# H07R1x_Backend.net
KiCad netlist of a schematic drawn in Altium Designer
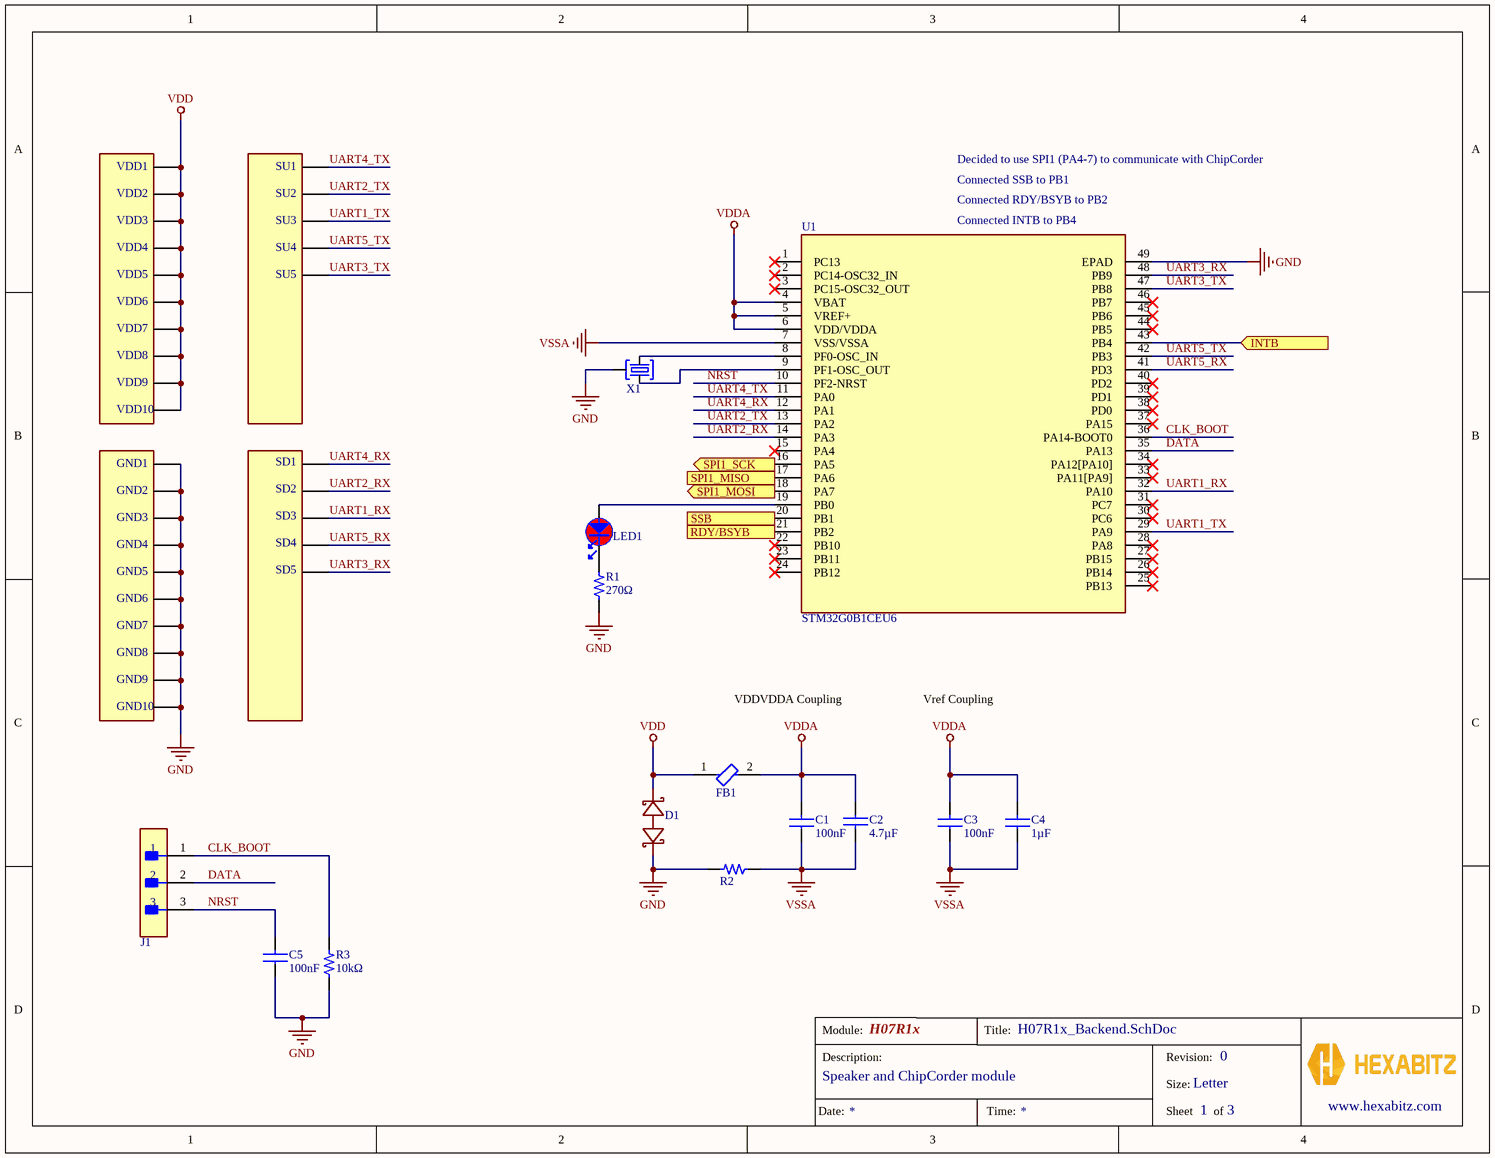
[diagram p0: H07R1x_Backend.SchDoc]

(export (version "E")
  (design (tool "Eeschema 10.0.6"))
  (components
    (comp (ref "C1")
      (value "100nF")
      (footprint "C0603")
      (fields
        (field (name "MANUFACTURER") "Samsung Electro-Mechanics")
        (field (name "MANUFACTURER PART NUMBER") "CL10B104KA8NNNC")
        (field (name "TOLERANCE") "10%")
      )
      (libsource (lib "Hexabitz Altium Library") (part "generic Capacitor"))
    )
    (comp (ref "C2")
      (value "4.7µF")
      (footprint "C0805")
      (fields
        (field (name "MANUFACTURER") "Samsung Electro-Mechanics")
        (field (name "MANUFACTURER PART NUMBER") "CL21X475KAQNNNE")
        (field (name "TOLERANCE") "10%")
      )
      (libsource (lib "Hexabitz Altium Library") (part "generic Capacitor"))
    )
    (comp (ref "C3")
      (value "100nF")
      (footprint "C0603")
      (fields
        (field (name "MANUFACTURER") "Samsung Electro-Mechanics")
        (field (name "MANUFACTURER PART NUMBER") "CL10B104KA8NNNC")
        (field (name "TOLERANCE") "10%")
      )
      (libsource (lib "Hexabitz Altium Library") (part "generic Capacitor"))
    )
    (comp (ref "C4")
      (value "1µF")
      (footprint "C0805")
      (description "Ceramic Capacitor, Ceramic, 16V, 10% +Tol, 10% -Tol, X7R, 15% TC, 1uF, Surface Mount, 0805")
      (fields
        (field (name "MANUFACTURER") "Yageo Group")
        (field (name "MANUFACTURER PART NUMBER") "CC0805KKX7R7BB105")
      )
      (libsource (lib "Hexabitz Altium Library") (part "generic Capacitor"))
    )
    (comp (ref "C5")
      (value "100nF")
      (footprint "C0603")
      (fields
        (field (name "MANUFACTURER") "Samsung Electro-Mechanics")
        (field (name "MANUFACTURER PART NUMBER") "CL10B104KA8NNNC")
        (field (name "TOLERANCE") "10%")
      )
      (libsource (lib "Hexabitz Altium Library") (part "generic Capacitor"))
    )
    (comp (ref "D1")
      (value "CDSOD323-T03SC")
      (footprint "SOD2513X114N")
      (description "A 3V, 350W, bi-directional, standard capacitance, SOD323 pkg TVS Diode ¦ Bourns CDSOD323-T03SC")
      (fields (field (name "MANUFACTURER") "Bourns"))
      (libsource (lib "Hexabitz Altium Library") (part "CDSOD323-T03SC"))
    )
    (comp (ref "FB1")
      (value "MMZ1608Y300B")
      (footprint "FP-MMZ1608-0_8-MFG")
      (description "Ferrite Beads 0603 30ohms 1500mA Signal Line AEC-Q200")
      (fields
        (field (name "MANUFACTURER") "TDK")
        (field (name "MANUFACTURER PART NUMBER") "MMZ1608Y300BTD25")
      )
      (libsource (lib "Hexabitz Altium Library") (part "MMZ1608Y300B"))
    )
    (comp (ref "GND1")
      (value "HEXABIT_UART_PORT")
      (footprint "HEXABIT_POWER_PORT_D")
      (libsource (lib "hexabitz_connectors.Library") (part "HEXABIT_POWER_PORT_D"))
    )
    (comp (ref "GND2")
      (value "HEXABIT_UART_PORT")
      (footprint "HEXABIT_POWER_PORT_D")
      (libsource (lib "hexabitz_connectors.Library") (part "HEXABIT_POWER_PORT_D"))
    )
    (comp (ref "GND3")
      (value "HEXABIT_UART_PORT")
      (footprint "HEXABIT_POWER_PORT_D_300R")
      (libsource (lib "hexabitz_connectors.Library") (part "HEXABIT_POWER_PORT_D_300R"))
    )
    (comp (ref "GND4")
      (value "HEXABIT_UART_PORT")
      (footprint "HEXABIT_POWER_PORT_D")
      (libsource (lib "hexabitz_connectors.Library") (part "HEXABIT_POWER_PORT_D"))
    )
    (comp (ref "GND5")
      (value "HEXABIT_UART_PORT")
      (footprint "HEXABIT_POWER_PORT_D")
      (libsource (lib "hexabitz_connectors.Library") (part "HEXABIT_POWER_PORT_D"))
    )
    (comp (ref "GND6")
      (value "HEXABIT_UART_PORT")
      (footprint "HEXABIT_POWER_PORT_D")
      (libsource (lib "hexabitz_connectors.Library") (part "HEXABIT_POWER_PORT_D"))
    )
    (comp (ref "GND7")
      (value "HEXABIT_UART_PORT")
      (footprint "HEXABIT_POWER_PORT_D")
      (libsource (lib "hexabitz_connectors.Library") (part "HEXABIT_POWER_PORT_D"))
    )
    (comp (ref "GND8")
      (value "HEXABIT_UART_PORT")
      (footprint "HEXABIT_POWER_PORT_D_300L")
      (libsource (lib "hexabitz_connectors.Library") (part "HEXABIT_POWER_PORT_D_300L"))
    )
    (comp (ref "GND9")
      (value "HEXABIT_UART_PORT")
      (footprint "HEXABIT_POWER_PORT_D")
      (libsource (lib "hexabitz_connectors.Library") (part "HEXABIT_POWER_PORT_D"))
    )
    (comp (ref "GND10")
      (value "HEXABIT_UART_PORT")
      (footprint "HEXABIT_POWER_PORT_D")
      (libsource (lib "hexabitz_connectors.Library") (part "HEXABIT_POWER_PORT_D"))
    )
    (comp (ref "J1")
      (value "TSW-103-14-G-S")
      (footprint "FP-TSW-103-14-G-S-MFG")
      (description "CONN HEADER VERT 3POS 2.54MM")
      (libsource (lib "Altium Content Vault") (part "cd3439d6ef35ae5d9b27ec4fdd3e828"))
    )
    (comp (ref "LED1")
      (value "VLMS1300-GS08")
      (footprint "FP-6_541-5092_01-4-MFG")
      (description "LED Uni-Color Super Red 639nm 2-Pin Chip 0603(1608Metric) T/R")
      (fields (field (name "MANUFACTURER") "Vishay Semiconductors"))
      (libsource (lib "Hexabitz Altium Library") (part "VLMS1300-GS08"))
    )
    (comp (ref "R1")
      (value "270Ω")
      (footprint "R0603")
      (description "Res Thick Film 0603 270 Ohm 5% 0.1W(1/10W) ±200ppm/C Pad SMD Automotive T/R")
      (fields
        (field (name "MANUFACTURER") "Panasonic")
        (field (name "MANUFACTURER PART NUMBER") "ERJ-3GEYJ271V")
      )
      (libsource (lib "") (part "generic Resistor_1"))
    )
    (comp (ref "R2")
      (value "Manufacturer Part Number")
      (footprint "R0603")
      (libsource (lib "Hexabitz Altium Library") (part "generic Resistor"))
    )
    (comp (ref "R3")
      (value "10kΩ")
      (footprint "R0603")
      (description "100mW Thick Film Resistors ±100ppm/℃ ±1% 10kΩ 0603 Chip Resistor - Surface Mount ROHS")
      (fields
        (field (name "MANUFACTURER") "Yageo Group")
        (field (name "MANUFACTURER PART NUMBER") "RC0603FR-0710KL")
      )
      (libsource (lib "") (part "generic Resistor_2"))
    )
    (comp (ref "SD1")
      (value "HEXABIT_UART_PORT")
      (footprint "HEXABIT_UART_PORT_D")
      (libsource (lib "hexabitz_connectors.Library") (part "HEXABIT_UART_PORT_D"))
    )
    (comp (ref "SD2")
      (value "HEXABIT_UART_PORT")
      (footprint "HEXABIT_UART_PORT_D")
      (libsource (lib "hexabitz_connectors.Library") (part "HEXABIT_UART_PORT_D"))
    )
    (comp (ref "SD3")
      (value "HEXABIT_UART_PORT")
      (footprint "HEXABIT_UART_PORT_D")
      (libsource (lib "hexabitz_connectors.Library") (part "HEXABIT_UART_PORT_D"))
    )
    (comp (ref "SD4")
      (value "HEXABIT_UART_PORT")
      (footprint "HEXABIT_UART_PORT_D")
      (libsource (lib "hexabitz_connectors.Library") (part "HEXABIT_UART_PORT_D"))
    )
    (comp (ref "SD5")
      (value "HEXABIT_UART_PORT")
      (footprint "HEXABIT_UART_PORT_D")
      (libsource (lib "hexabitz_connectors.Library") (part "HEXABIT_UART_PORT_D"))
    )
    (comp (ref "SU1")
      (value "HEXABIT_UART_PORT")
      (footprint "HEXABIT_UART_PORT_U")
      (libsource (lib "hexabitz_connectors.Library") (part "HEXABIT_UART_PORT_U"))
    )
    (comp (ref "SU2")
      (value "HEXABIT_UART_PORT")
      (footprint "HEXABIT_UART_PORT_U")
      (libsource (lib "hexabitz_connectors.Library") (part "HEXABIT_UART_PORT_U"))
    )
    (comp (ref "SU3")
      (value "HEXABIT_UART_PORT")
      (footprint "HEXABIT_UART_PORT_U")
      (libsource (lib "hexabitz_connectors.Library") (part "HEXABIT_UART_PORT_U"))
    )
    (comp (ref "SU4")
      (value "HEXABIT_UART_PORT")
      (footprint "HEXABIT_UART_PORT_U")
      (libsource (lib "hexabitz_connectors.Library") (part "HEXABIT_UART_PORT_U"))
    )
    (comp (ref "SU5")
      (value "HEXABIT_UART_PORT")
      (footprint "HEXABIT_UART_PORT_U")
      (libsource (lib "hexabitz_connectors.Library") (part "HEXABIT_UART_PORT_U"))
    )
    (comp (ref "U1")
      (value "STM32G0B1CEU6")
      (footprint "QFN50P700X700X65-49N-D")
      (description "MCU 32-bit ARM Cortex M0+ RISC 512KB Flash 1.8V/2.5V/3.3V 48-Pin UFQFPN EP Tray")
      (fields
        (field (name "MANUFACTURER") "STMicroelectronics")
        (field (name "MANUFACTURER PART NUMBER") "STM32G0B1CEU6")
      )
      (libsource (lib "Hexabitz Altium Library") (part "STM32G0B1CEU6"))
    )
    (comp (ref "VDD1")
      (value "HEXABIT_UART_PORT")
      (footprint "HEXABIT_POWER_PORT_U")
      (libsource (lib "hexabitz_connectors.Library") (part "HEXABIT_POWER_PORT_U"))
    )
    (comp (ref "VDD2")
      (value "HEXABIT_UART_PORT")
      (footprint "HEXABIT_POWER_PORT_U")
      (libsource (lib "hexabitz_connectors.Library") (part "HEXABIT_POWER_PORT_U"))
    )
    (comp (ref "VDD3")
      (value "HEXABIT_UART_PORT")
      (footprint "HEXABIT_POWER_PORT_U_300R")
      (libsource (lib "hexabitz_connectors.Library") (part "HEXABIT_POWER_PORT_U_300R"))
    )
    (comp (ref "VDD4")
      (value "HEXABIT_UART_PORT")
      (footprint "HEXABIT_POWER_PORT_U")
      (libsource (lib "hexabitz_connectors.Library") (part "HEXABIT_POWER_PORT_U"))
    )
    (comp (ref "VDD5")
      (value "HEXABIT_UART_PORT")
      (footprint "HEXABIT_POWER_PORT_U")
      (libsource (lib "hexabitz_connectors.Library") (part "HEXABIT_POWER_PORT_U"))
    )
    (comp (ref "VDD6")
      (value "HEXABIT_UART_PORT")
      (footprint "HEXABIT_POWER_PORT_U")
      (libsource (lib "hexabitz_connectors.Library") (part "HEXABIT_POWER_PORT_U"))
    )
    (comp (ref "VDD7")
      (value "HEXABIT_UART_PORT")
      (footprint "HEXABIT_POWER_PORT_U")
      (libsource (lib "hexabitz_connectors.Library") (part "HEXABIT_POWER_PORT_U"))
    )
    (comp (ref "VDD8")
      (value "HEXABIT_UART_PORT")
      (footprint "HEXABIT_POWER_PORT_U_300L")
      (libsource (lib "hexabitz_connectors.Library") (part "HEXABIT_POWER_PORT_U_300L"))
    )
    (comp (ref "VDD9")
      (value "HEXABIT_UART_PORT")
      (footprint "HEXABIT_POWER_PORT_U")
      (libsource (lib "hexabitz_connectors.Library") (part "HEXABIT_POWER_PORT_U"))
    )
    (comp (ref "VDD10")
      (value "HEXABIT_UART_PORT")
      (footprint "HEXABIT_POWER_PORT_U")
      (libsource (lib "hexabitz_connectors.Library") (part "HEXABIT_POWER_PORT_U"))
    )
    (comp (ref "X1")
      (value "CSTCE8M00G52Z-R0")
      (footprint "XTALL_CSTCE8M00G52")
      (description "Ceramic Resonator 8MHz ±0.5% (Tol) ±0.2% (Stability) 10pF 40Ohm 3-Pin CSMD T/R")
      (fields (field (name "MANUFACTURER") "Murata") (field (name "TOLERANCE") "0.5%"))
      (libsource (lib "Hexabitz Altium Library") (part "CSTCE8M00G52Z-R0"))
    )
  )
  (nets
    (net (code "1") (name "/CLK_BOOT") (class "Default")
      (node (ref "J1") (pin "1") (pinfunction "1_1") (pintype "passive"))
      (node (ref "R3") (pin "1") (pinfunction "1_1") (pintype "passive"))
      (node (ref "U1") (pin "36") (pinfunction "PA14-BOOT0_36") (pintype "passive"))
    )
    (net (code "2") (name "/DATA") (class "Default")
      (node (ref "J1") (pin "2") (pinfunction "2_2") (pintype "passive"))
      (node (ref "U1") (pin "35") (pinfunction "PA13_35") (pintype "passive"))
    )
    (net (code "3") (name "/INTB") (class "Default")
      (node (ref "U1") (pin "43") (pinfunction "PB4_43") (pintype "passive"))
    )
    (net (code "4") (name "/NRST") (class "Default")
      (node (ref "C5") (pin "2") (pinfunction "2_2") (pintype "passive"))
      (node (ref "J1") (pin "3") (pinfunction "3_3") (pintype "passive"))
      (node (ref "U1") (pin "10") (pinfunction "PF2-NRST_10") (pintype "passive"))
    )
    (net (code "5") (name "/RDY{slash}BSYB") (class "Default")
      (node (ref "U1") (pin "21") (pinfunction "PB2_21") (pintype "passive"))
    )
    (net (code "6") (name "/SPI1_MISO") (class "Default")
      (node (ref "U1") (pin "17") (pinfunction "PA6_17") (pintype "passive"))
    )
    (net (code "7") (name "/SPI1_MOSI") (class "Default")
      (node (ref "U1") (pin "18") (pinfunction "PA7_18") (pintype "passive"))
    )
    (net (code "8") (name "/SPI1_SCK") (class "Default")
      (node (ref "U1") (pin "16") (pinfunction "PA5_16") (pintype "passive"))
    )
    (net (code "9") (name "/SSB") (class "Default")
      (node (ref "U1") (pin "20") (pinfunction "PB1_20") (pintype "passive"))
    )
    (net (code "10") (name "/UART1_RX") (class "Default")
      (node (ref "SD3") (pin "UART_D") (pinfunction "UART_D_UART_D") (pintype "passive"))
      (node (ref "U1") (pin "32") (pinfunction "PA10_32") (pintype "passive"))
    )
    (net (code "11") (name "/UART1_TX") (class "Default")
      (node (ref "SU3") (pin "UART_U") (pinfunction "UART_U_UART_U") (pintype "passive"))
      (node (ref "U1") (pin "29") (pinfunction "PA9_29") (pintype "passive"))
    )
    (net (code "12") (name "/UART2_RX") (class "Default")
      (node (ref "SD2") (pin "UART_D") (pinfunction "UART_D_UART_D") (pintype "passive"))
      (node (ref "U1") (pin "14") (pinfunction "PA3_14") (pintype "passive"))
    )
    (net (code "13") (name "/UART2_TX") (class "Default")
      (node (ref "SU2") (pin "UART_U") (pinfunction "UART_U_UART_U") (pintype "passive"))
      (node (ref "U1") (pin "13") (pinfunction "PA2_13") (pintype "passive"))
    )
    (net (code "14") (name "/UART3_RX") (class "Default")
      (node (ref "SD5") (pin "UART_D") (pinfunction "UART_D_UART_D") (pintype "passive"))
      (node (ref "U1") (pin "48") (pinfunction "PB9_48") (pintype "passive"))
    )
    (net (code "15") (name "/UART3_TX") (class "Default")
      (node (ref "SU5") (pin "UART_U") (pinfunction "UART_U_UART_U") (pintype "passive"))
      (node (ref "U1") (pin "47") (pinfunction "PB8_47") (pintype "passive"))
    )
    (net (code "16") (name "/UART4_RX") (class "Default")
      (node (ref "SD1") (pin "UART_D") (pinfunction "UART_D_UART_D") (pintype "passive"))
      (node (ref "U1") (pin "12") (pinfunction "PA1_12") (pintype "passive"))
    )
    (net (code "17") (name "/UART4_TX") (class "Default")
      (node (ref "SU1") (pin "UART_U") (pinfunction "UART_U_UART_U") (pintype "passive"))
      (node (ref "U1") (pin "11") (pinfunction "PA0_11") (pintype "passive"))
    )
    (net (code "18") (name "/UART5_RX") (class "Default")
      (node (ref "SD4") (pin "UART_D") (pinfunction "UART_D_UART_D") (pintype "passive"))
      (node (ref "U1") (pin "41") (pinfunction "PD3_41") (pintype "passive"))
    )
    (net (code "19") (name "/UART5_TX") (class "Default")
      (node (ref "SU4") (pin "UART_U") (pinfunction "UART_U_UART_U") (pintype "passive"))
      (node (ref "U1") (pin "42") (pinfunction "PB3_42") (pintype "passive"))
    )
    (net (code "20") (name "GND") (class "Default")
      (node (ref "C5") (pin "1") (pinfunction "1_1") (pintype "passive"))
      (node (ref "D1") (pin "1") (pinfunction "A_1") (pintype "passive"))
      (node (ref "GND1") (pin "Pwr_D") (pinfunction "Pwr_D_Pwr_D") (pintype "passive"))
      (node (ref "GND10") (pin "Pwr_D") (pinfunction "Pwr_D_Pwr_D") (pintype "passive"))
      (node (ref "GND2") (pin "Pwr_D") (pinfunction "Pwr_D_Pwr_D") (pintype "passive"))
      (node (ref "GND3") (pin "Pwr_D") (pinfunction "Pwr_D_Pwr_D") (pintype "passive"))
      (node (ref "GND4") (pin "Pwr_D") (pinfunction "Pwr_D_Pwr_D") (pintype "passive"))
      (node (ref "GND5") (pin "Pwr_D") (pinfunction "Pwr_D_Pwr_D") (pintype "passive"))
      (node (ref "GND6") (pin "Pwr_D") (pinfunction "Pwr_D_Pwr_D") (pintype "passive"))
      (node (ref "GND7") (pin "Pwr_D") (pinfunction "Pwr_D_Pwr_D") (pintype "passive"))
      (node (ref "GND8") (pin "Pwr_D") (pinfunction "Pwr_D_Pwr_D") (pintype "passive"))
      (node (ref "GND9") (pin "Pwr_D") (pinfunction "Pwr_D_Pwr_D") (pintype "passive"))
      (node (ref "R1") (pin "1") (pinfunction "1_1") (pintype "passive"))
      (node (ref "R2") (pin "1") (pinfunction "1_1") (pintype "passive"))
      (node (ref "R3") (pin "2") (pinfunction "2_2") (pintype "passive"))
      (node (ref "U1") (pin "49") (pinfunction "EPAD_49") (pintype "passive"))
      (node (ref "X1") (pin "P$2") (pinfunction "2_P$2") (pintype "passive"))
    )
    (net (code "21") (name "Net-(LED1-Pad1)") (class "Default")
      (node (ref "LED1") (pin "1") (pintype "passive"))
      (node (ref "R1") (pin "2") (pinfunction "2_2") (pintype "passive"))
    )
    (net (code "22") (name "Net-(U1-PB0)") (class "Default")
      (node (ref "LED1") (pin "2") (pintype "passive"))
      (node (ref "U1") (pin "19") (pinfunction "PB0_19") (pintype "passive"))
    )
    (net (code "23") (name "Net-(U1-PF0-OSC_IN)") (class "Default")
      (node (ref "U1") (pin "8") (pinfunction "PF0-OSC_IN_8") (pintype "passive"))
      (node (ref "X1") (pin "P$3") (pinfunction "3_P$3") (pintype "passive"))
    )
    (net (code "24") (name "Net-(U1-PF1-OSC_OUT)") (class "Default")
      (node (ref "U1") (pin "9") (pinfunction "PF1-OSC_OUT_9") (pintype "passive"))
      (node (ref "X1") (pin "P$1") (pinfunction "1_P$1") (pintype "passive"))
    )
    (net (code "25") (name "VDD") (class "Default")
      (node (ref "D1") (pin "2") (pinfunction "C_2") (pintype "passive"))
      (node (ref "FB1") (pin "1") (pinfunction "1_1") (pintype "passive"))
      (node (ref "VDD1") (pin "Pwr_U") (pinfunction "Pwr_U_Pwr_U") (pintype "passive"))
      (node (ref "VDD10") (pin "Pwr_U") (pinfunction "Pwr_U_Pwr_U") (pintype "passive"))
      (node (ref "VDD2") (pin "Pwr_U") (pinfunction "Pwr_U_Pwr_U") (pintype "passive"))
      (node (ref "VDD3") (pin "Pwr_U") (pinfunction "Pwr_U_Pwr_U") (pintype "passive"))
      (node (ref "VDD4") (pin "Pwr_U") (pinfunction "Pwr_U_Pwr_U") (pintype "passive"))
      (node (ref "VDD5") (pin "Pwr_U") (pinfunction "Pwr_U_Pwr_U") (pintype "passive"))
      (node (ref "VDD6") (pin "Pwr_U") (pinfunction "Pwr_U_Pwr_U") (pintype "passive"))
      (node (ref "VDD7") (pin "Pwr_U") (pinfunction "Pwr_U_Pwr_U") (pintype "passive"))
      (node (ref "VDD8") (pin "Pwr_U") (pinfunction "Pwr_U_Pwr_U") (pintype "passive"))
      (node (ref "VDD9") (pin "Pwr_U") (pinfunction "Pwr_U_Pwr_U") (pintype "passive"))
    )
    (net (code "26") (name "VDDA") (class "Default")
      (node (ref "C1") (pin "2") (pinfunction "2_2") (pintype "passive"))
      (node (ref "C2") (pin "1") (pinfunction "1_1") (pintype "passive"))
      (node (ref "C3") (pin "2") (pinfunction "2_2") (pintype "passive"))
      (node (ref "C4") (pin "2") (pinfunction "2_2") (pintype "passive"))
      (node (ref "FB1") (pin "2") (pinfunction "2_2") (pintype "passive"))
      (node (ref "U1") (pin "4") (pinfunction "VBAT_4") (pintype "passive"))
      (node (ref "U1") (pin "5") (pinfunction "VREF+_5") (pintype "passive"))
      (node (ref "U1") (pin "6") (pinfunction "VDD/VDDA_6") (pintype "passive"))
    )
    (net (code "27") (name "VSSA") (class "Default")
      (node (ref "C1") (pin "1") (pinfunction "1_1") (pintype "passive"))
      (node (ref "C2") (pin "2") (pinfunction "2_2") (pintype "passive"))
      (node (ref "C3") (pin "1") (pinfunction "1_1") (pintype "passive"))
      (node (ref "C4") (pin "1") (pinfunction "1_1") (pintype "passive"))
      (node (ref "R2") (pin "2") (pinfunction "2_2") (pintype "passive"))
      (node (ref "U1") (pin "7") (pinfunction "VSS/VSSA_7") (pintype "passive"))
    )
    (net (code "28") (name "unconnected-(U1-PA4-Pad15)") (class "Default")
      (node (ref "U1") (pin "15") (pinfunction "PA4_15") (pintype "passive+no_connect"))
    )
    (net (code "29") (name "unconnected-(U1-PA8-Pad28)") (class "Default")
      (node (ref "U1") (pin "28") (pinfunction "PA8_28") (pintype "passive+no_connect"))
    )
    (net (code "30") (name "unconnected-(U1-PA11[PA9]-Pad33)") (class "Default")
      (node (ref "U1") (pin "33") (pinfunction "PA11[PA9]_33") (pintype "passive+no_connect"))
    )
    (net (code "31") (name "unconnected-(U1-PA12[PA10]-Pad34)") (class "Default")
      (node (ref "U1") (pin "34") (pinfunction "PA12[PA10]_34") (pintype "passive+no_connect"))
    )
    (net (code "32") (name "unconnected-(U1-PA15-Pad37)") (class "Default")
      (node (ref "U1") (pin "37") (pinfunction "PA15_37") (pintype "passive+no_connect"))
    )
    (net (code "33") (name "unconnected-(U1-PB5-Pad44)") (class "Default")
      (node (ref "U1") (pin "44") (pinfunction "PB5_44") (pintype "passive+no_connect"))
    )
    (net (code "34") (name "unconnected-(U1-PB6-Pad45)") (class "Default")
      (node (ref "U1") (pin "45") (pinfunction "PB6_45") (pintype "passive+no_connect"))
    )
    (net (code "35") (name "unconnected-(U1-PB7-Pad46)") (class "Default")
      (node (ref "U1") (pin "46") (pinfunction "PB7_46") (pintype "passive+no_connect"))
    )
    (net (code "36") (name "unconnected-(U1-PB10-Pad22)") (class "Default")
      (node (ref "U1") (pin "22") (pinfunction "PB10_22") (pintype "passive+no_connect"))
    )
    (net (code "37") (name "unconnected-(U1-PB11-Pad23)") (class "Default")
      (node (ref "U1") (pin "23") (pinfunction "PB11_23") (pintype "passive+no_connect"))
    )
    (net (code "38") (name "unconnected-(U1-PB12-Pad24)") (class "Default")
      (node (ref "U1") (pin "24") (pinfunction "PB12_24") (pintype "passive+no_connect"))
    )
    (net (code "39") (name "unconnected-(U1-PB13-Pad25)") (class "Default")
      (node (ref "U1") (pin "25") (pinfunction "PB13_25") (pintype "passive+no_connect"))
    )
    (net (code "40") (name "unconnected-(U1-PB14-Pad26)") (class "Default")
      (node (ref "U1") (pin "26") (pinfunction "PB14_26") (pintype "passive+no_connect"))
    )
    (net (code "41") (name "unconnected-(U1-PB15-Pad27)") (class "Default")
      (node (ref "U1") (pin "27") (pinfunction "PB15_27") (pintype "passive+no_connect"))
    )
    (net (code "42") (name "unconnected-(U1-PC6-Pad30)") (class "Default")
      (node (ref "U1") (pin "30") (pinfunction "PC6_30") (pintype "passive+no_connect"))
    )
    (net (code "43") (name "unconnected-(U1-PC7-Pad31)") (class "Default")
      (node (ref "U1") (pin "31") (pinfunction "PC7_31") (pintype "passive+no_connect"))
    )
    (net (code "44") (name "unconnected-(U1-PC13-Pad1)") (class "Default")
      (node (ref "U1") (pin "1") (pinfunction "PC13_1") (pintype "passive+no_connect"))
    )
    (net (code "45") (name "unconnected-(U1-PC14-OSC32_IN-Pad2)") (class "Default")
      (node (ref "U1") (pin "2") (pinfunction "PC14-OSC32_IN_2") (pintype "passive+no_connect"))
    )
    (net (code "46") (name "unconnected-(U1-PC15-OSC32_OUT-Pad3)") (class "Default")
      (node (ref "U1") (pin "3") (pinfunction "PC15-OSC32_OUT_3") (pintype "passive+no_connect"))
    )
    (net (code "47") (name "unconnected-(U1-PD0-Pad38)") (class "Default")
      (node (ref "U1") (pin "38") (pinfunction "PD0_38") (pintype "passive+no_connect"))
    )
    (net (code "48") (name "unconnected-(U1-PD1-Pad39)") (class "Default")
      (node (ref "U1") (pin "39") (pinfunction "PD1_39") (pintype "passive+no_connect"))
    )
    (net (code "49") (name "unconnected-(U1-PD2-Pad40)") (class "Default")
      (node (ref "U1") (pin "40") (pinfunction "PD2_40") (pintype "passive+no_connect"))
    )
  )
)
